# Sim7600.net
KiCad netlist of a schematic drawn in Altium Designer
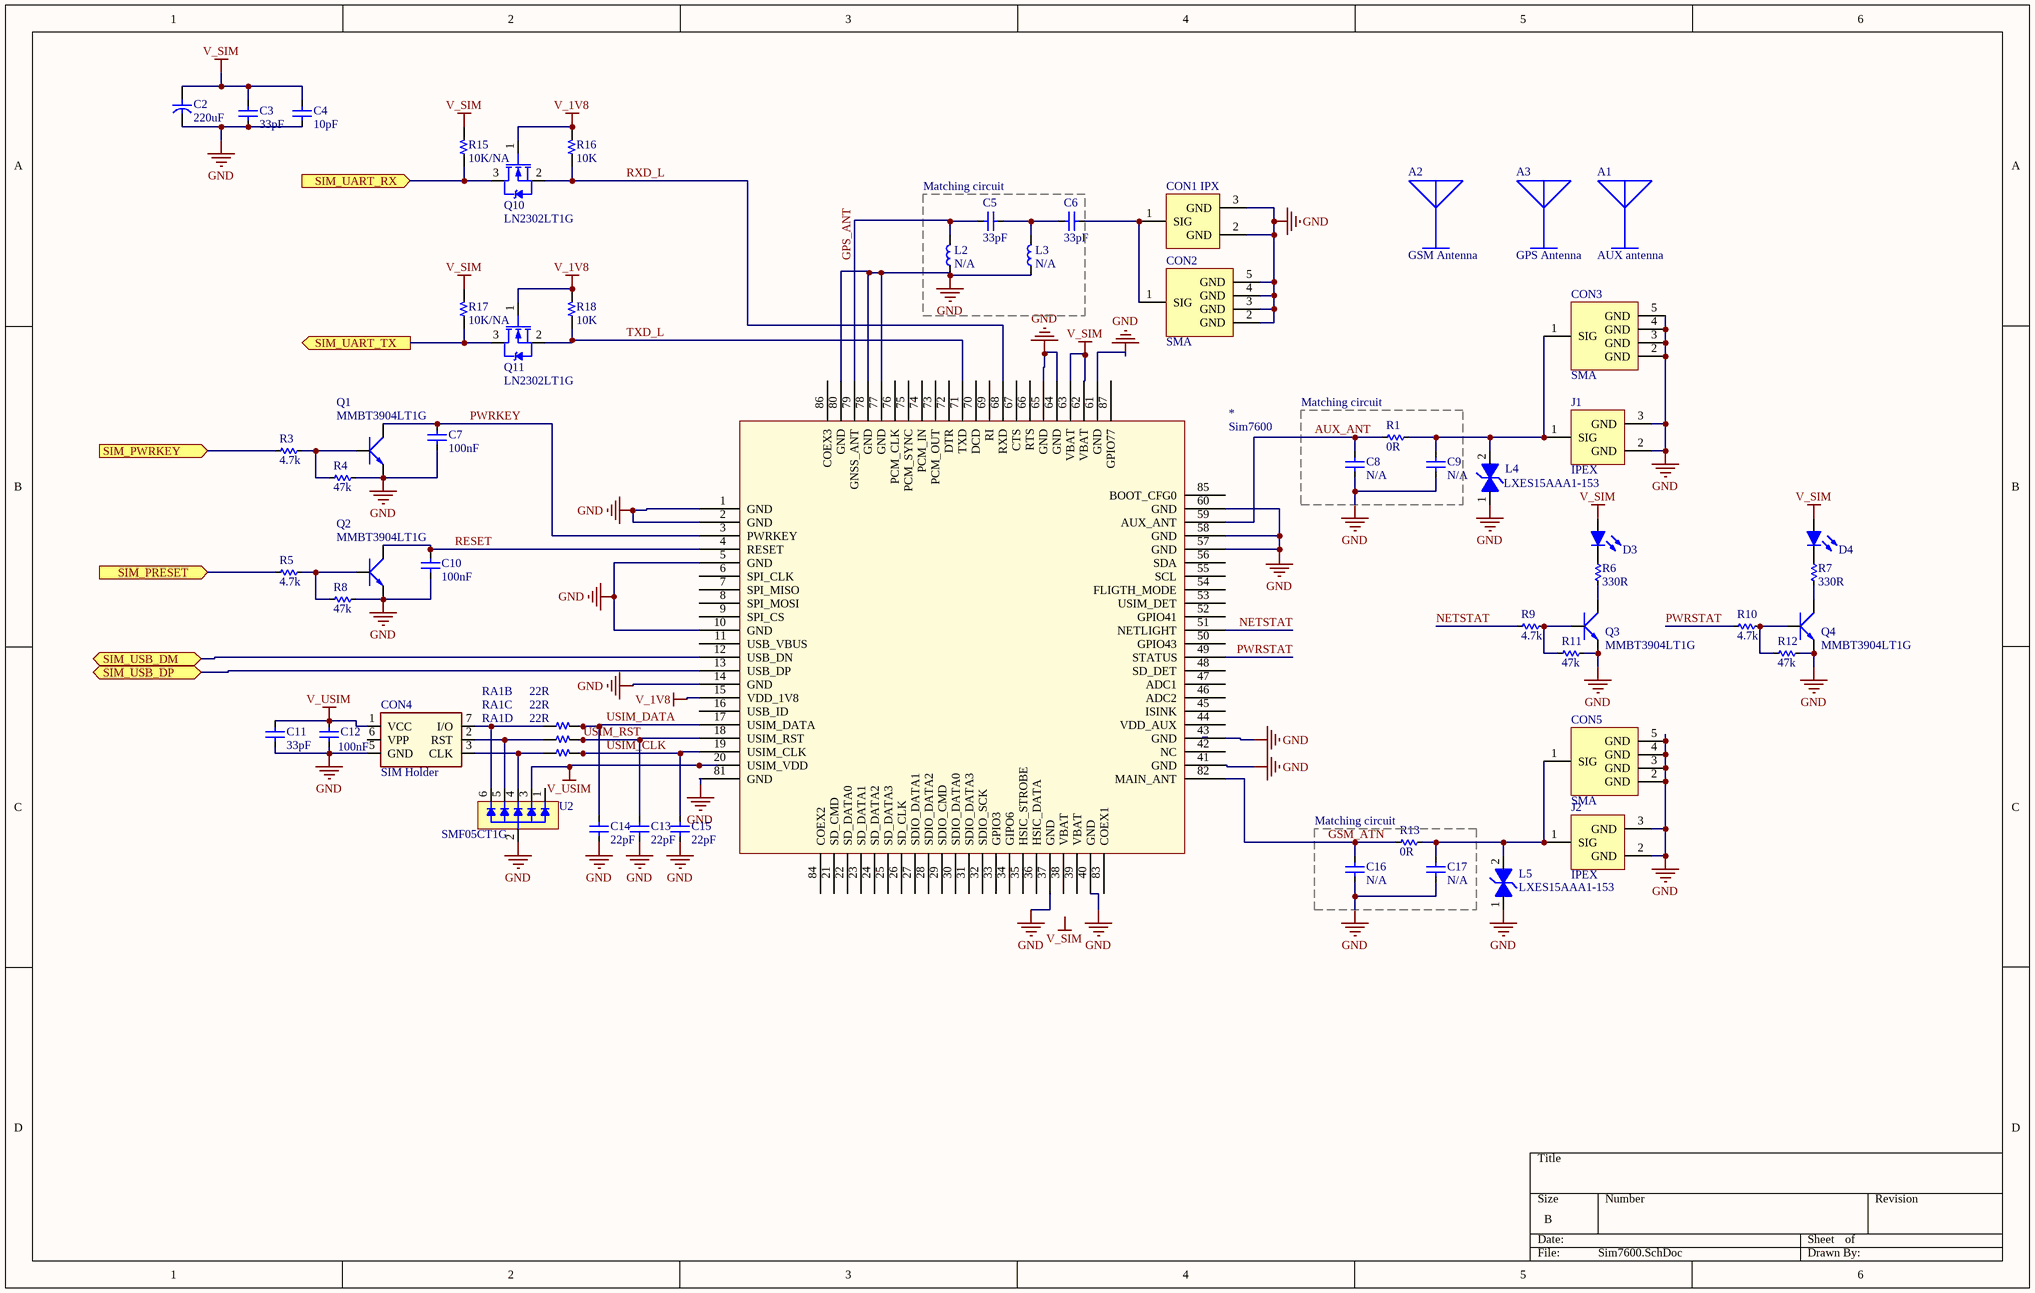
[diagram p0: Sim7600.SchDoc]

(export (version "E")
  (design (tool "Eeschema 10.0.6"))
  (components
    (comp (ref "*") (value "Sim7600") (footprint "Sim7600") (libsource (lib "Sim7600") (part "Sim7600")))
    (comp (ref "A1")
      (value "AUX antenna")
      (footprint "Antenna")
      (description "Antenna")
      (libsource (lib "car_logger_libs") (part "Antenna"))
    )
    (comp (ref "A2")
      (value "GSM Antenna")
      (footprint "Antenna")
      (description "Antenna")
      (libsource (lib "car_logger_libs") (part "Antenna"))
    )
    (comp (ref "A3")
      (value "GPS Antenna")
      (footprint "Antenna")
      (description "Antenna")
      (libsource (lib "car_logger_libs") (part "Antenna"))
    )
    (comp (ref "C2")
      (value "220uF")
      (footprint "C SMD ALU (D8)")
      (description "CAP TANT POLY 100UF 6.3V 1210")
      (fields
        (field (name "MANUFACTURER") "AVX Corporation")
        (field (name "MANUFACTURER PART NUMBER") "TCJB107M006R0055")
      )
      (libsource (lib "ChipFC_Lib") (part "Capacitor"))
    )
    (comp (ref "C3")
      (value "33pF")
      (footprint "CC 0603")
      (description "CAP CER 33PF 100V C0G/NP0 0603")
      (fields
        (field (name "MANUFACTURER") "Murata Electronics")
        (field (name "MANUFACTURER PART NUMBER") "GCM1885C2A330JA16D")
      )
      (libsource (lib "car_logger_libs") (part "Capacitor NP"))
    )
    (comp (ref "C4")
      (value "10pF")
      (footprint "CC 0603")
      (description "CAP CER 10PF 100V C0G/NP0 0603")
      (fields
        (field (name "MANUFACTURER") "Murata Electronics")
        (field (name "MANUFACTURER PART NUMBER") "GCM1885C2A100JA16D")
      )
      (libsource (lib "car_logger_libs") (part "Capacitor NP"))
    )
    (comp (ref "C5")
      (value "33pF")
      (footprint "CC 0603")
      (description "CAP CER 33PF 100V C0G/NP0 0603")
      (fields
        (field (name "MANUFACTURER") "Murata Electronics")
        (field (name "MANUFACTURER PART NUMBER") "GCM1885C2A330JA16D")
      )
      (libsource (lib "car_logger_libs") (part "Capacitor NP"))
    )
    (comp (ref "C6")
      (value "33pF")
      (footprint "CC 0603")
      (description "CAP CER 33PF 100V C0G/NP0 0603")
      (fields
        (field (name "MANUFACTURER") "Murata Electronics")
        (field (name "MANUFACTURER PART NUMBER") "GCM1885C2A330JA16D")
      )
      (libsource (lib "car_logger_libs") (part "Capacitor NP"))
    )
    (comp (ref "C7")
      (value "100nF")
      (footprint "CC 0603")
      (description "CAP CER 0.1UF 16V X7R 0603")
      (fields
        (field (name "MANUFACTURER") "Murata Electronics")
        (field (name "MANUFACTURER PART NUMBER") "GCJ188R71C104KA01D")
      )
      (libsource (lib "car_logger_libs") (part "Capacitor NP"))
    )
    (comp (ref "C8")
      (value "N/A")
      (footprint "CC 0603")
      (description "CAP N/A")
      (libsource (lib "car_logger_libs") (part "Capacitor NP"))
    )
    (comp (ref "C9")
      (value "N/A")
      (footprint "CC 0603")
      (description "CAP N/A")
      (libsource (lib "car_logger_libs") (part "Capacitor NP"))
    )
    (comp (ref "C10")
      (value "100nF")
      (footprint "CC 0603")
      (description "CAP CER 0.1UF 16V X7R 0603")
      (fields
        (field (name "MANUFACTURER") "Murata Electronics")
        (field (name "MANUFACTURER PART NUMBER") "GCJ188R71C104KA01D")
      )
      (libsource (lib "car_logger_libs") (part "Capacitor NP"))
    )
    (comp (ref "C11")
      (value "33pF")
      (footprint "CC 0603")
      (description "CAP CER 33PF 100V C0G/NP0 0603")
      (fields
        (field (name "MANUFACTURER") "Murata Electronics")
        (field (name "MANUFACTURER PART NUMBER") "GCM1885C2A330JA16D")
      )
      (libsource (lib "car_logger_libs") (part "Capacitor NP"))
    )
    (comp (ref "C12")
      (value "100nF")
      (footprint "CC 0603")
      (description "CAP CER 0.1UF 16V X7R 0603")
      (fields
        (field (name "MANUFACTURER") "Murata Electronics")
        (field (name "MANUFACTURER PART NUMBER") "GCJ188R71C104KA01D")
      )
      (libsource (lib "car_logger_libs") (part "Capacitor NP"))
    )
    (comp (ref "C13")
      (value "22pF")
      (footprint "CC 0603")
      (description "CAP CER 33PF 100V C0G/NP0 0603")
      (fields
        (field (name "MANUFACTURER") "Murata Electronics")
        (field (name "MANUFACTURER PART NUMBER") "GCM1885C2A330JA16D")
      )
      (libsource (lib "car_logger_libs") (part "Capacitor NP"))
    )
    (comp (ref "C14")
      (value "22pF")
      (footprint "CC 0603")
      (description "CAP CER 33PF 100V C0G/NP0 0603")
      (fields
        (field (name "MANUFACTURER") "Murata Electronics")
        (field (name "MANUFACTURER PART NUMBER") "GCM1885C2A330JA16D")
      )
      (libsource (lib "car_logger_libs") (part "Capacitor NP"))
    )
    (comp (ref "C15")
      (value "22pF")
      (footprint "CC 0603")
      (description "CAP CER 33PF 100V C0G/NP0 0603")
      (fields
        (field (name "MANUFACTURER") "Murata Electronics")
        (field (name "MANUFACTURER PART NUMBER") "GCM1885C2A330JA16D")
      )
      (libsource (lib "car_logger_libs") (part "Capacitor NP"))
    )
    (comp (ref "C16")
      (value "N/A")
      (footprint "CC 0603")
      (description "CAP N/A")
      (libsource (lib "car_logger_libs") (part "Capacitor NP"))
    )
    (comp (ref "C17")
      (value "N/A")
      (footprint "CC 0603")
      (description "CAP N/A")
      (libsource (lib "car_logger_libs") (part "Capacitor NP"))
    )
    (comp (ref "CON1")
      (value "IPX")
      (footprint "CONN/IPX/SMD")
      (libsource (lib "chipfc_altium_libs") (part "CON IPX"))
    )
    (comp (ref "CON2")
      (value "SMA")
      (footprint "CONN/SMA/RA")
      (description "SMA connectors")
      (libsource (lib "chipfc_altium_libs") (part "CON SMA"))
    )
    (comp (ref "CON3")
      (value "SMA")
      (footprint "CONN/SMA/RA")
      (description "SMA connectors")
      (libsource (lib "chipfc_altium_libs") (part "CON SMA"))
    )
    (comp (ref "CON4")
      (value "SIM Holder")
      (footprint "CON SIM Holder C707")
      (description "SIM Card holder, 6 pins")
      (libsource (lib "chipfc_altium_libs") (part "SIM holder 6 pin"))
    )
    (comp (ref "CON5")
      (value "SMA")
      (footprint "CONN/SMA/RA")
      (description "SMA connectors")
      (libsource (lib "chipfc_altium_libs") (part "CON SMA"))
    )
    (comp (ref "D3")
      (value "LED GREEN")
      (footprint "Led 0603 - green")
      (description "LED GREEN DIFFUSED 0603 SMD")
      (fields
        (field (name "MANUFACTURER") "Rohm Semiconductor")
        (field (name "MANUFACTURER PART NUMBER") "SML-D12P8WT86")
      )
      (libsource (lib "chipfc_altium_libs") (part "Led"))
    )
    (comp (ref "D4")
      (value "LED RED")
      (footprint "Led 0603 - red")
      (description "LED RED DIFFUSED 0603 SMD")
      (fields
        (field (name "MANUFACTURER") "Rohm Semiconductor")
        (field (name "MANUFACTURER PART NUMBER") "SML-D12U8WT86")
      )
      (libsource (lib "chipfc_altium_libs") (part "Led"))
    )
    (comp (ref "J1")
      (value "IPEX")
      (footprint "CONN/IPX/SMD")
      (description "CONN UMC RCPT STR 50 OHM SMD")
      (fields
        (field (name "MANUFACTURER") "Taoglas Limited")
        (field (name "MANUFACTURER PART NUMBER") "RECE.20279.001E.01")
      )
      (libsource (lib "chipfc_altium_libs") (part "CON IPX"))
    )
    (comp (ref "J2")
      (value "IPEX")
      (footprint "CONN/IPX/SMD")
      (description "CONN UMC RCPT STR 50 OHM SMD")
      (fields
        (field (name "MANUFACTURER") "Taoglas Limited")
        (field (name "MANUFACTURER PART NUMBER") "RECE.20279.001E.01")
      )
      (libsource (lib "chipfc_altium_libs") (part "CON IPX"))
    )
    (comp (ref "L2")
      (value "N/A")
      (footprint "LL 0603")
      (description "IND N/A")
      (libsource (lib "car_logger_libs") (part "Inductor"))
    )
    (comp (ref "L3")
      (value "N/A")
      (footprint "LL 0603")
      (description "IND N/A")
      (libsource (lib "car_logger_libs") (part "Inductor"))
    )
    (comp (ref "L4")
      (value "LXES15AAA1-153")
      (footprint "C 0603")
      (description "Clamp Ipp Tvs Diode Surface Mount 1005")
      (fields (field (name "MF") "Murata") (field (name "DIGI-KEY_PART_NUMBER") "490-13210-1-ND"))
      (libsource (lib "LXES15AAA1-153") (part "LXES15AAA1-153"))
    )
    (comp (ref "L5")
      (value "LXES15AAA1-153")
      (footprint "C 0603")
      (description "Clamp Ipp Tvs Diode Surface Mount 1005")
      (fields (field (name "MF") "Murata") (field (name "DIGI-KEY_PART_NUMBER") "490-13210-1-ND"))
      (libsource (lib "LXES15AAA1-153") (part "LXES15AAA1-153"))
    )
    (comp (ref "Q1")
      (value "MMBT3904LT1G")
      (footprint "SOT-23")
      (description "TRANS NPN 40V 0.2A SOT23")
      (fields (field (name "MANUFACTURER") "ON Semiconductor"))
      (libsource (lib "car_logger_libs") (part "MMBT3904LT1G"))
    )
    (comp (ref "Q2")
      (value "MMBT3904LT1G")
      (footprint "SOT-23")
      (description "TRANS NPN 40V 0.2A SOT23")
      (fields (field (name "MANUFACTURER") "ON Semiconductor"))
      (libsource (lib "car_logger_libs") (part "MMBT3904LT1G"))
    )
    (comp (ref "Q3")
      (value "MMBT3904LT1G")
      (footprint "SOT-23")
      (description "TRANS NPN 40V 0.2A SOT23")
      (fields (field (name "MANUFACTURER") "ON Semiconductor"))
      (libsource (lib "car_logger_libs") (part "MMBT3904LT1G"))
    )
    (comp (ref "Q4")
      (value "MMBT3904LT1G")
      (footprint "SOT-23")
      (description "TRANS NPN 40V 0.2A SOT23")
      (fields (field (name "MANUFACTURER") "ON Semiconductor"))
      (libsource (lib "car_logger_libs") (part "MMBT3904LT1G"))
    )
    (comp (ref "Q10")
      (value "LN2302LT1G")
      (footprint "SOT-23")
      (description "Mosfet N")
      (libsource (lib "chipfc_altium_libs") (part "Mosfet N"))
    )
    (comp (ref "Q11")
      (value "LN2302LT1G")
      (footprint "SOT-23")
      (description "Mosfet N")
      (libsource (lib "chipfc_altium_libs") (part "Mosfet N"))
    )
    (comp (ref "R1")
      (value "0R")
      (footprint "RR 0603")
      (description "RES SMD 0 OHM JUMPER 1/10W 0603")
      (fields
        (field (name "MANUFACTURER") "Panasonic Industrial Devices")
        (field (name "MANUFACTURER PART NUMBER") "ERJ-3GEY0R00V")
      )
      (libsource (lib "car_logger_libs") (part "Resistors"))
    )
    (comp (ref "R3")
      (value "4.7k")
      (footprint "RR 0603")
      (description "RES SMD 4.7K OHM 1% 1/10W 0603")
      (fields
        (field (name "MANUFACTURER") "Panasonic Industrial Devices")
        (field (name "MANUFACTURER PART NUMBER") "ERJ-3EKF4701V")
      )
      (libsource (lib "car_logger_libs") (part "Resistors"))
    )
    (comp (ref "R4")
      (value "47k")
      (footprint "RR 0603")
      (description "RES SMD 47K OHM 5% 1/10W 0603")
      (fields
        (field (name "MANUFACTURER") "Panasonic Industrial Devices")
        (field (name "MANUFACTURER PART NUMBER") "ERJ-3GEYJ473V")
      )
      (libsource (lib "car_logger_libs") (part "Resistors"))
    )
    (comp (ref "R5")
      (value "4.7k")
      (footprint "RR 0603")
      (description "RES SMD 4.7K OHM 1% 1/10W 0603")
      (fields
        (field (name "MANUFACTURER") "Panasonic Industrial Devices")
        (field (name "MANUFACTURER PART NUMBER") "ERJ-3EKF4701V")
      )
      (libsource (lib "car_logger_libs") (part "Resistors"))
    )
    (comp (ref "R6")
      (value "330R")
      (footprint "RR 0603")
      (description "RES SMD 330 OHM 5% 1/10W 0603")
      (fields
        (field (name "MANUFACTURER") "Panasonic Industrial Devices")
        (field (name "MANUFACTURER PART NUMBER") "ERJ-3GEYJ331V")
      )
      (libsource (lib "car_logger_libs") (part "Resistors"))
    )
    (comp (ref "R7")
      (value "330R")
      (footprint "RR 0603")
      (description "RES SMD 330 OHM 5% 1/10W 0603")
      (fields
        (field (name "MANUFACTURER") "Panasonic Industrial Devices")
        (field (name "MANUFACTURER PART NUMBER") "ERJ-3GEYJ331V")
      )
      (libsource (lib "car_logger_libs") (part "Resistors"))
    )
    (comp (ref "R8")
      (value "47k")
      (footprint "RR 0603")
      (description "RES SMD 47K OHM 5% 1/10W 0603")
      (fields
        (field (name "MANUFACTURER") "Panasonic Industrial Devices")
        (field (name "MANUFACTURER PART NUMBER") "ERJ-3GEYJ473V")
      )
      (libsource (lib "car_logger_libs") (part "Resistors"))
    )
    (comp (ref "R9")
      (value "4.7k")
      (footprint "RR 0603")
      (description "RES SMD 4.7K OHM 1% 1/10W 0603")
      (fields
        (field (name "MANUFACTURER") "Panasonic Industrial Devices")
        (field (name "MANUFACTURER PART NUMBER") "ERJ-3EKF4701V")
      )
      (libsource (lib "car_logger_libs") (part "Resistors"))
    )
    (comp (ref "R10")
      (value "4.7k")
      (footprint "RR 0603")
      (description "RES SMD 4.7K OHM 1% 1/10W 0603")
      (fields
        (field (name "MANUFACTURER") "Panasonic Industrial Devices")
        (field (name "MANUFACTURER PART NUMBER") "ERJ-3EKF4701V")
      )
      (libsource (lib "car_logger_libs") (part "Resistors"))
    )
    (comp (ref "R11")
      (value "47k")
      (footprint "RR 0603")
      (description "RES SMD 47K OHM 5% 1/10W 0603")
      (fields
        (field (name "MANUFACTURER") "Panasonic Industrial Devices")
        (field (name "MANUFACTURER PART NUMBER") "ERJ-3GEYJ473V")
      )
      (libsource (lib "car_logger_libs") (part "Resistors"))
    )
    (comp (ref "R12")
      (value "47k")
      (footprint "RR 0603")
      (description "RES SMD 47K OHM 5% 1/10W 0603")
      (fields
        (field (name "MANUFACTURER") "Panasonic Industrial Devices")
        (field (name "MANUFACTURER PART NUMBER") "ERJ-3GEYJ473V")
      )
      (libsource (lib "car_logger_libs") (part "Resistors"))
    )
    (comp (ref "R13")
      (value "0R")
      (footprint "RR 0603")
      (description "RES SMD 0 OHM JUMPER 1/10W 0603")
      (fields
        (field (name "MANUFACTURER") "Panasonic Industrial Devices")
        (field (name "MANUFACTURER PART NUMBER") "ERJ-3GEY0R00V")
      )
      (libsource (lib "car_logger_libs") (part "Resistors"))
    )
    (comp (ref "R15")
      (value "10K/NA")
      (footprint "R 0603")
      (description "Resistor")
      (libsource (lib "chipfc_altium_libs") (part "Resistor"))
    )
    (comp (ref "R16")
      (value "10K")
      (footprint "R 0603")
      (description "Resistor")
      (libsource (lib "chipfc_altium_libs") (part "Resistor"))
    )
    (comp (ref "R17")
      (value "10K/NA")
      (footprint "R 0603")
      (description "Resistor")
      (libsource (lib "chipfc_altium_libs") (part "Resistor"))
    )
    (comp (ref "R18")
      (value "10K")
      (footprint "R 0603")
      (description "Resistor")
      (libsource (lib "chipfc_altium_libs") (part "Resistor"))
    )
    (comp (ref "RA1")
      (value "22R")
      (footprint "RAx4 1206 (3216)")
      (libsource (lib "chipfc_altium_libs") (part "Resistor Array x4"))
    )
    (comp (ref "U2")
      (value "SMF05CT1G")
      (footprint "SOT-363-6")
      (description "TVS DIODE 5V 12.5V SC88")
      (fields (field (name "MANUFACTURER") "ON Semiconductor"))
      (libsource (lib "car_logger_libs") (part "SMF05C"))
    )
  )
  (nets
    (net (code "1") (name "/AUX_ANT") (class "Default")
      (node (ref "*") (pin "59") (pinfunction "AUX_ANT_59") (pintype "passive"))
      (node (ref "C8") (pin "2") (pinfunction "2_2") (pintype "passive"))
      (node (ref "R1") (pin "2") (pinfunction "2_2") (pintype "passive"))
    )
    (net (code "2") (name "/GPS_ANT") (class "Default")
      (node (ref "*") (pin "79") (pinfunction "GNSS_ANT_79") (pintype "passive"))
      (node (ref "C5") (pin "2") (pinfunction "2_2") (pintype "passive"))
      (node (ref "L2") (pin "2") (pinfunction "2_2") (pintype "passive"))
    )
    (net (code "3") (name "/GSM_ATN") (class "Default")
      (node (ref "*") (pin "82") (pinfunction "MAIN_ANT_82") (pintype "passive"))
      (node (ref "C16") (pin "2") (pinfunction "2_2") (pintype "passive"))
      (node (ref "R13") (pin "2") (pinfunction "2_2") (pintype "passive"))
    )
    (net (code "4") (name "/NETSTAT") (class "Default")
      (node (ref "*") (pin "51") (pinfunction "NETLIGHT_51") (pintype "passive"))
      (node (ref "R9") (pin "1") (pinfunction "1_1") (pintype "passive"))
    )
    (net (code "5") (name "/PWRKEY") (class "Default")
      (node (ref "*") (pin "3") (pinfunction "PWRKEY_3") (pintype "passive"))
      (node (ref "C7") (pin "1") (pinfunction "1_1") (pintype "passive"))
      (node (ref "Q1") (pin "3") (pinfunction "C_3") (pintype "passive"))
    )
    (net (code "6") (name "/PWRSTAT") (class "Default")
      (node (ref "*") (pin "49") (pinfunction "STATUS_49") (pintype "passive"))
      (node (ref "R10") (pin "1") (pinfunction "1_1") (pintype "passive"))
    )
    (net (code "7") (name "/RESET") (class "Default")
      (node (ref "*") (pin "4") (pinfunction "RESET_4") (pintype "passive"))
      (node (ref "C10") (pin "1") (pinfunction "1_1") (pintype "passive"))
      (node (ref "Q2") (pin "3") (pinfunction "C_3") (pintype "passive"))
    )
    (net (code "8") (name "/RXD_L") (class "Default")
      (node (ref "*") (pin "68") (pinfunction "RXD_68") (pintype "passive"))
      (node (ref "Q10") (pin "2") (pinfunction "S_2") (pintype "passive"))
      (node (ref "R16") (pin "1") (pinfunction "1_1") (pintype "passive"))
    )
    (net (code "9") (name "/SIM_PRESET") (class "Default")
      (node (ref "R5") (pin "1") (pinfunction "1_1") (pintype "passive"))
    )
    (net (code "10") (name "/SIM_PWRKEY") (class "Default")
      (node (ref "R3") (pin "1") (pinfunction "1_1") (pintype "passive"))
    )
    (net (code "11") (name "/SIM_UART_RX") (class "Default")
      (node (ref "Q10") (pin "3") (pinfunction "D_3") (pintype "passive"))
      (node (ref "R15") (pin "1") (pinfunction "1_1") (pintype "passive"))
    )
    (net (code "12") (name "/SIM_UART_TX") (class "Default")
      (node (ref "Q11") (pin "3") (pinfunction "D_3") (pintype "passive"))
      (node (ref "R17") (pin "1") (pinfunction "1_1") (pintype "passive"))
    )
    (net (code "13") (name "/SIM_USB_DM") (class "Default")
      (node (ref "*") (pin "12") (pinfunction "USB_DN_12") (pintype "passive"))
    )
    (net (code "14") (name "/SIM_USB_DP") (class "Default")
      (node (ref "*") (pin "13") (pinfunction "USB_DP_13") (pintype "passive"))
    )
    (net (code "15") (name "/TXD_L") (class "Default")
      (node (ref "*") (pin "71") (pinfunction "TXD_71") (pintype "passive"))
      (node (ref "Q11") (pin "2") (pinfunction "S_2") (pintype "passive"))
      (node (ref "R18") (pin "1") (pinfunction "1_1") (pintype "passive"))
    )
    (net (code "16") (name "/USIM_CLK") (class "Default")
      (node (ref "*") (pin "19") (pinfunction "USIM_CLK_19") (pintype "passive"))
      (node (ref "C15") (pin "1") (pinfunction "1_1") (pintype "passive"))
      (node (ref "RA1") (pin "5") (pinfunction "5_5") (pintype "passive"))
    )
    (net (code "17") (name "/USIM_DATA") (class "Default")
      (node (ref "*") (pin "17") (pinfunction "USIM_DATA_17") (pintype "passive"))
      (node (ref "C14") (pin "1") (pinfunction "1_1") (pintype "passive"))
      (node (ref "RA1") (pin "7") (pinfunction "7_7") (pintype "passive"))
    )
    (net (code "18") (name "/USIM_RST") (class "Default")
      (node (ref "*") (pin "18") (pinfunction "USIM_RST_18") (pintype "passive"))
      (node (ref "C13") (pin "1") (pinfunction "1_1") (pintype "passive"))
      (node (ref "RA1") (pin "6") (pinfunction "6_6") (pintype "passive"))
    )
    (net (code "19") (name "GND") (class "Default")
      (node (ref "*") (pin "1") (pinfunction "GND_1") (pintype "passive"))
      (node (ref "*") (pin "10") (pinfunction "GND_10") (pintype "passive"))
      (node (ref "*") (pin "14") (pinfunction "GND_14") (pintype "passive"))
      (node (ref "*") (pin "2") (pinfunction "GND_2") (pintype "passive"))
      (node (ref "*") (pin "37") (pinfunction "GND_37") (pintype "passive"))
      (node (ref "*") (pin "40") (pinfunction "GND_40") (pintype "passive"))
      (node (ref "*") (pin "41") (pinfunction "GND_41") (pintype "passive"))
      (node (ref "*") (pin "43") (pinfunction "GND_43") (pintype "passive"))
      (node (ref "*") (pin "5") (pinfunction "GND_5") (pintype "passive"))
      (node (ref "*") (pin "57") (pinfunction "GND_57") (pintype "passive"))
      (node (ref "*") (pin "58") (pinfunction "GND_58") (pintype "passive"))
      (node (ref "*") (pin "60") (pinfunction "GND_60") (pintype "passive"))
      (node (ref "*") (pin "61") (pinfunction "GND_61") (pintype "passive"))
      (node (ref "*") (pin "64") (pinfunction "GND_64") (pintype "passive"))
      (node (ref "*") (pin "65") (pinfunction "GND_65") (pintype "passive"))
      (node (ref "*") (pin "77") (pinfunction "GND_77") (pintype "passive"))
      (node (ref "*") (pin "78") (pinfunction "GND_78") (pintype "passive"))
      (node (ref "*") (pin "80") (pinfunction "GND_80") (pintype "passive"))
      (node (ref "*") (pin "81") (pinfunction "GND_81") (pintype "passive"))
      (node (ref "C10") (pin "2") (pinfunction "2_2") (pintype "passive"))
      (node (ref "C11") (pin "2") (pinfunction "2_2") (pintype "passive"))
      (node (ref "C12") (pin "2") (pinfunction "2_2") (pintype "passive"))
      (node (ref "C13") (pin "2") (pinfunction "2_2") (pintype "passive"))
      (node (ref "C14") (pin "2") (pinfunction "2_2") (pintype "passive"))
      (node (ref "C15") (pin "2") (pinfunction "2_2") (pintype "passive"))
      (node (ref "C16") (pin "1") (pinfunction "1_1") (pintype "passive"))
      (node (ref "C17") (pin "1") (pinfunction "1_1") (pintype "passive"))
      (node (ref "C2") (pin "2") (pinfunction "2_2") (pintype "passive"))
      (node (ref "C3") (pin "1") (pinfunction "1_1") (pintype "passive"))
      (node (ref "C4") (pin "1") (pinfunction "1_1") (pintype "passive"))
      (node (ref "C7") (pin "2") (pinfunction "2_2") (pintype "passive"))
      (node (ref "C8") (pin "1") (pinfunction "1_1") (pintype "passive"))
      (node (ref "C9") (pin "1") (pinfunction "1_1") (pintype "passive"))
      (node (ref "CON1") (pin "2") (pinfunction "GND_2") (pintype "passive"))
      (node (ref "CON1") (pin "3") (pinfunction "GND_3") (pintype "passive"))
      (node (ref "CON2") (pin "2") (pinfunction "GND_2") (pintype "passive"))
      (node (ref "CON2") (pin "3") (pinfunction "GND_3") (pintype "passive"))
      (node (ref "CON2") (pin "4") (pinfunction "GND_4") (pintype "passive"))
      (node (ref "CON2") (pin "5") (pinfunction "GND_5") (pintype "passive"))
      (node (ref "CON3") (pin "2") (pinfunction "GND_2") (pintype "passive"))
      (node (ref "CON3") (pin "3") (pinfunction "GND_3") (pintype "passive"))
      (node (ref "CON3") (pin "4") (pinfunction "GND_4") (pintype "passive"))
      (node (ref "CON3") (pin "5") (pinfunction "GND_5") (pintype "passive"))
      (node (ref "CON4") (pin "5") (pinfunction "GND_5") (pintype "power_in"))
      (node (ref "CON5") (pin "2") (pinfunction "GND_2") (pintype "passive"))
      (node (ref "CON5") (pin "3") (pinfunction "GND_3") (pintype "passive"))
      (node (ref "CON5") (pin "4") (pinfunction "GND_4") (pintype "passive"))
      (node (ref "CON5") (pin "5") (pinfunction "GND_5") (pintype "passive"))
      (node (ref "J1") (pin "2") (pinfunction "GND_2") (pintype "passive"))
      (node (ref "J1") (pin "3") (pinfunction "GND_3") (pintype "passive"))
      (node (ref "J2") (pin "2") (pinfunction "GND_2") (pintype "passive"))
      (node (ref "J2") (pin "3") (pinfunction "GND_3") (pintype "passive"))
      (node (ref "L2") (pin "1") (pinfunction "1_1") (pintype "passive"))
      (node (ref "L3") (pin "1") (pinfunction "1_1") (pintype "passive"))
      (node (ref "L4") (pin "1") (pinfunction "1_1") (pintype "passive"))
      (node (ref "L5") (pin "1") (pinfunction "1_1") (pintype "passive"))
      (node (ref "Q1") (pin "2") (pinfunction "E_2") (pintype "passive"))
      (node (ref "Q2") (pin "2") (pinfunction "E_2") (pintype "passive"))
      (node (ref "Q3") (pin "2") (pinfunction "E_2") (pintype "passive"))
      (node (ref "Q4") (pin "2") (pinfunction "E_2") (pintype "passive"))
      (node (ref "R11") (pin "2") (pinfunction "2_2") (pintype "passive"))
      (node (ref "R12") (pin "2") (pinfunction "2_2") (pintype "passive"))
      (node (ref "R4") (pin "2") (pinfunction "2_2") (pintype "passive"))
      (node (ref "R8") (pin "2") (pinfunction "2_2") (pintype "passive"))
      (node (ref "U2") (pin "2") (pinfunction "A_2") (pintype "passive"))
    )
    (net (code "20") (name "Net-(C5-Pad1)") (class "Default")
      (node (ref "C5") (pin "1") (pinfunction "1_1") (pintype "passive"))
      (node (ref "C6") (pin "2") (pinfunction "2_2") (pintype "passive"))
      (node (ref "L3") (pin "2") (pinfunction "2_2") (pintype "passive"))
    )
    (net (code "21") (name "Net-(CON1-SIG)") (class "Default")
      (node (ref "C6") (pin "1") (pinfunction "1_1") (pintype "passive"))
      (node (ref "CON1") (pin "1") (pinfunction "SIG_1") (pintype "passive"))
      (node (ref "CON2") (pin "1") (pinfunction "SIG_1") (pintype "passive"))
    )
    (net (code "22") (name "Net-(CON3-SIG)") (class "Default")
      (node (ref "C9") (pin "2") (pinfunction "2_2") (pintype "passive"))
      (node (ref "CON3") (pin "1") (pinfunction "SIG_1") (pintype "passive"))
      (node (ref "J1") (pin "1") (pinfunction "SIG_1") (pintype "passive"))
      (node (ref "L4") (pin "2") (pinfunction "2_2") (pintype "passive"))
      (node (ref "R1") (pin "1") (pinfunction "1_1") (pintype "passive"))
    )
    (net (code "23") (name "Net-(CON4-CLK)") (class "Default")
      (node (ref "CON4") (pin "3") (pinfunction "CLK_3") (pintype "passive"))
      (node (ref "RA1") (pin "4") (pinfunction "4_4") (pintype "passive"))
      (node (ref "U2") (pin "4") (pinfunction "K4_4") (pintype "passive"))
    )
    (net (code "24") (name "Net-(CON4-I{slash}O)") (class "Default")
      (node (ref "CON4") (pin "7") (pinfunction "I/O_7") (pintype "passive"))
      (node (ref "RA1") (pin "2") (pinfunction "2_2") (pintype "passive"))
      (node (ref "U2") (pin "6") (pinfunction "K6_6") (pintype "passive"))
    )
    (net (code "25") (name "Net-(CON4-RST)") (class "Default")
      (node (ref "CON4") (pin "2") (pinfunction "RST_2") (pintype "passive"))
      (node (ref "RA1") (pin "3") (pinfunction "3_3") (pintype "passive"))
      (node (ref "U2") (pin "5") (pinfunction "K5_5") (pintype "passive"))
    )
    (net (code "26") (name "Net-(CON5-SIG)") (class "Default")
      (node (ref "C17") (pin "2") (pinfunction "2_2") (pintype "passive"))
      (node (ref "CON5") (pin "1") (pinfunction "SIG_1") (pintype "passive"))
      (node (ref "J2") (pin "1") (pinfunction "SIG_1") (pintype "passive"))
      (node (ref "L5") (pin "2") (pinfunction "2_2") (pintype "passive"))
      (node (ref "R13") (pin "1") (pinfunction "1_1") (pintype "passive"))
    )
    (net (code "27") (name "Net-(D3-K)") (class "Default")
      (node (ref "D3") (pin "2") (pinfunction "K_2") (pintype "passive"))
      (node (ref "R6") (pin "2") (pinfunction "2_2") (pintype "passive"))
    )
    (net (code "28") (name "Net-(D4-K)") (class "Default")
      (node (ref "D4") (pin "2") (pinfunction "K_2") (pintype "passive"))
      (node (ref "R7") (pin "2") (pinfunction "2_2") (pintype "passive"))
    )
    (net (code "29") (name "Net-(Q1-B)") (class "Default")
      (node (ref "Q1") (pin "1") (pinfunction "B_1") (pintype "passive"))
      (node (ref "R3") (pin "2") (pinfunction "2_2") (pintype "passive"))
      (node (ref "R4") (pin "1") (pinfunction "1_1") (pintype "passive"))
    )
    (net (code "30") (name "Net-(Q2-B)") (class "Default")
      (node (ref "Q2") (pin "1") (pinfunction "B_1") (pintype "passive"))
      (node (ref "R5") (pin "2") (pinfunction "2_2") (pintype "passive"))
      (node (ref "R8") (pin "1") (pinfunction "1_1") (pintype "passive"))
    )
    (net (code "31") (name "Net-(Q3-B)") (class "Default")
      (node (ref "Q3") (pin "1") (pinfunction "B_1") (pintype "passive"))
      (node (ref "R11") (pin "1") (pinfunction "1_1") (pintype "passive"))
      (node (ref "R9") (pin "2") (pinfunction "2_2") (pintype "passive"))
    )
    (net (code "32") (name "Net-(Q3-C)") (class "Default")
      (node (ref "Q3") (pin "3") (pinfunction "C_3") (pintype "passive"))
      (node (ref "R6") (pin "1") (pinfunction "1_1") (pintype "passive"))
    )
    (net (code "33") (name "Net-(Q4-B)") (class "Default")
      (node (ref "Q4") (pin "1") (pinfunction "B_1") (pintype "passive"))
      (node (ref "R10") (pin "2") (pinfunction "2_2") (pintype "passive"))
      (node (ref "R12") (pin "1") (pinfunction "1_1") (pintype "passive"))
    )
    (net (code "34") (name "Net-(Q4-C)") (class "Default")
      (node (ref "Q4") (pin "3") (pinfunction "C_3") (pintype "passive"))
      (node (ref "R7") (pin "1") (pinfunction "1_1") (pintype "passive"))
    )
    (net (code "35") (name "V_1V8") (class "Default")
      (node (ref "*") (pin "15") (pinfunction "VDD_1V8_15") (pintype "passive"))
      (node (ref "Q10") (pin "1") (pinfunction "G_1") (pintype "passive"))
      (node (ref "Q11") (pin "1") (pinfunction "G_1") (pintype "passive"))
      (node (ref "R16") (pin "2") (pinfunction "2_2") (pintype "passive"))
      (node (ref "R18") (pin "2") (pinfunction "2_2") (pintype "passive"))
    )
    (net (code "36") (name "V_SIM") (class "Default")
      (node (ref "*") (pin "62") (pinfunction "VBAT_62") (pintype "passive"))
      (node (ref "*") (pin "63") (pinfunction "VBAT_63") (pintype "passive"))
      (node (ref "C2") (pin "1") (pinfunction "1_1") (pintype "passive"))
      (node (ref "C3") (pin "2") (pinfunction "2_2") (pintype "passive"))
      (node (ref "C4") (pin "2") (pinfunction "2_2") (pintype "passive"))
      (node (ref "D3") (pin "1") (pinfunction "A_1") (pintype "passive"))
      (node (ref "D4") (pin "1") (pinfunction "A_1") (pintype "passive"))
      (node (ref "R15") (pin "2") (pinfunction "2_2") (pintype "passive"))
      (node (ref "R17") (pin "2") (pinfunction "2_2") (pintype "passive"))
    )
    (net (code "37") (name "V_USIM") (class "Default")
      (node (ref "*") (pin "20") (pinfunction "USIM_VDD_20") (pintype "passive"))
      (node (ref "C11") (pin "1") (pinfunction "1_1") (pintype "passive"))
      (node (ref "C12") (pin "1") (pinfunction "1_1") (pintype "passive"))
      (node (ref "CON4") (pin "1") (pinfunction "VCC_1") (pintype "power_in"))
      (node (ref "U2") (pin "3") (pinfunction "K3_3") (pintype "passive"))
    )
    (net (code "38") (name "unconnected-(*-ADC1-Pad47)") (class "Default")
      (node (ref "*") (pin "47") (pinfunction "ADC1_47") (pintype "passive"))
    )
    (net (code "39") (name "unconnected-(*-ADC2-Pad46)") (class "Default")
      (node (ref "*") (pin "46") (pinfunction "ADC2_46") (pintype "passive"))
    )
    (net (code "40") (name "unconnected-(*-BOOT_CFG0-Pad85)") (class "Default")
      (node (ref "*") (pin "85") (pinfunction "BOOT_CFG0_85") (pintype "passive"))
    )
    (net (code "41") (name "unconnected-(*-COEX1-Pad83)") (class "Default")
      (node (ref "*") (pin "83") (pinfunction "COEX1_83") (pintype "passive"))
    )
    (net (code "42") (name "unconnected-(*-COEX2-Pad84)") (class "Default")
      (node (ref "*") (pin "84") (pinfunction "COEX2_84") (pintype "passive"))
    )
    (net (code "43") (name "unconnected-(*-COEX3-Pad86)") (class "Default")
      (node (ref "*") (pin "86") (pinfunction "COEX3_86") (pintype "passive"))
    )
    (net (code "44") (name "unconnected-(*-CTS-Pad67)") (class "Default")
      (node (ref "*") (pin "67") (pinfunction "CTS_67") (pintype "passive"))
    )
    (net (code "45") (name "unconnected-(*-DCD-Pad70)") (class "Default")
      (node (ref "*") (pin "70") (pinfunction "DCD_70") (pintype "passive"))
    )
    (net (code "46") (name "unconnected-(*-DTR-Pad72)") (class "Default")
      (node (ref "*") (pin "72") (pinfunction "DTR_72") (pintype "passive"))
    )
    (net (code "47") (name "unconnected-(*-FLIGTH_MODE-Pad54)") (class "Default")
      (node (ref "*") (pin "54") (pinfunction "FLIGTH_MODE_54") (pintype "passive"))
    )
    (net (code "48") (name "unconnected-(*-GIPO6-Pad34)") (class "Default")
      (node (ref "*") (pin "34") (pinfunction "GIPO6_34") (pintype "passive"))
    )
    (net (code "49") (name "unconnected-(*-GPIO3-Pad33)") (class "Default")
      (node (ref "*") (pin "33") (pinfunction "GPIO3_33") (pintype "passive"))
    )
    (net (code "50") (name "unconnected-(*-GPIO41-Pad52)") (class "Default")
      (node (ref "*") (pin "52") (pinfunction "GPIO41_52") (pintype "passive"))
    )
    (net (code "51") (name "unconnected-(*-GPIO43-Pad50)") (class "Default")
      (node (ref "*") (pin "50") (pinfunction "GPIO43_50") (pintype "passive"))
    )
    (net (code "52") (name "unconnected-(*-GPIO77-Pad87)") (class "Default")
      (node (ref "*") (pin "87") (pinfunction "GPIO77_87") (pintype "passive"))
    )
    (net (code "53") (name "unconnected-(*-HSIC_DATA-Pad36)") (class "Default")
      (node (ref "*") (pin "36") (pinfunction "HSIC_DATA_36") (pintype "passive"))
    )
    (net (code "54") (name "unconnected-(*-HSIC_STROBE-Pad35)") (class "Default")
      (node (ref "*") (pin "35") (pinfunction "HSIC_STROBE_35") (pintype "passive"))
    )
    (net (code "55") (name "unconnected-(*-ISINK-Pad45)") (class "Default")
      (node (ref "*") (pin "45") (pinfunction "ISINK_45") (pintype "passive"))
    )
    (net (code "56") (name "unconnected-(*-NC-Pad42)") (class "Default")
      (node (ref "*") (pin "42") (pinfunction "NC_42") (pintype "passive"))
    )
    (net (code "57") (name "unconnected-(*-PCM_CLK-Pad76)") (class "Default")
      (node (ref "*") (pin "76") (pinfunction "PCM_CLK_76") (pintype "passive"))
    )
    (net (code "58") (name "unconnected-(*-PCM_IN-Pad74)") (class "Default")
      (node (ref "*") (pin "74") (pinfunction "PCM_IN_74") (pintype "passive"))
    )
    (net (code "59") (name "unconnected-(*-PCM_OUT-Pad73)") (class "Default")
      (node (ref "*") (pin "73") (pinfunction "PCM_OUT_73") (pintype "passive"))
    )
    (net (code "60") (name "unconnected-(*-PCM_SYNC-Pad75)") (class "Default")
      (node (ref "*") (pin "75") (pinfunction "PCM_SYNC_75") (pintype "passive"))
    )
    (net (code "61") (name "unconnected-(*-RI-Pad69)") (class "Default")
      (node (ref "*") (pin "69") (pinfunction "RI_69") (pintype "passive"))
    )
    (net (code "62") (name "unconnected-(*-RTS-Pad66)") (class "Default")
      (node (ref "*") (pin "66") (pinfunction "RTS_66") (pintype "passive"))
    )
    (net (code "63") (name "unconnected-(*-SCL-Pad55)") (class "Default")
      (node (ref "*") (pin "55") (pinfunction "SCL_55") (pintype "passive"))
    )
    (net (code "64") (name "unconnected-(*-SDA-Pad56)") (class "Default")
      (node (ref "*") (pin "56") (pinfunction "SDA_56") (pintype "passive"))
    )
    (net (code "65") (name "unconnected-(*-SDIO_CMD-Pad29)") (class "Default")
      (node (ref "*") (pin "29") (pinfunction "SDIO_CMD_29") (pintype "passive"))
    )
    (net (code "66") (name "unconnected-(*-SDIO_DATA0-Pad30)") (class "Default")
      (node (ref "*") (pin "30") (pinfunction "SDIO_DATA0_30") (pintype "passive"))
    )
    (net (code "67") (name "unconnected-(*-SDIO_DATA1-Pad27)") (class "Default")
      (node (ref "*") (pin "27") (pinfunction "SDIO_DATA1_27") (pintype "passive"))
    )
    (net (code "68") (name "unconnected-(*-SDIO_DATA2-Pad28)") (class "Default")
      (node (ref "*") (pin "28") (pinfunction "SDIO_DATA2_28") (pintype "passive"))
    )
    (net (code "69") (name "unconnected-(*-SDIO_DATA3-Pad31)") (class "Default")
      (node (ref "*") (pin "31") (pinfunction "SDIO_DATA3_31") (pintype "passive"))
    )
    (net (code "70") (name "unconnected-(*-SDIO_SCK-Pad32)") (class "Default")
      (node (ref "*") (pin "32") (pinfunction "SDIO_SCK_32") (pintype "passive"))
    )
    (net (code "71") (name "unconnected-(*-SD_CLK-Pad26)") (class "Default")
      (node (ref "*") (pin "26") (pinfunction "SD_CLK_26") (pintype "passive"))
    )
    (net (code "72") (name "unconnected-(*-SD_CMD-Pad21)") (class "Default")
      (node (ref "*") (pin "21") (pinfunction "SD_CMD_21") (pintype "passive"))
    )
    (net (code "73") (name "unconnected-(*-SD_DATA0-Pad22)") (class "Default")
      (node (ref "*") (pin "22") (pinfunction "SD_DATA0_22") (pintype "passive"))
    )
    (net (code "74") (name "unconnected-(*-SD_DATA1-Pad23)") (class "Default")
      (node (ref "*") (pin "23") (pinfunction "SD_DATA1_23") (pintype "passive"))
    )
    (net (code "75") (name "unconnected-(*-SD_DATA2-Pad24)") (class "Default")
      (node (ref "*") (pin "24") (pinfunction "SD_DATA2_24") (pintype "passive"))
    )
    (net (code "76") (name "unconnected-(*-SD_DATA3-Pad25)") (class "Default")
      (node (ref "*") (pin "25") (pinfunction "SD_DATA3_25") (pintype "passive"))
    )
    (net (code "77") (name "unconnected-(*-SD_DET-Pad48)") (class "Default")
      (node (ref "*") (pin "48") (pinfunction "SD_DET_48") (pintype "passive"))
    )
    (net (code "78") (name "unconnected-(*-SPI_CLK-Pad6)") (class "Default")
      (node (ref "*") (pin "6") (pinfunction "SPI_CLK_6") (pintype "passive"))
    )
    (net (code "79") (name "unconnected-(*-SPI_CS-Pad9)") (class "Default")
      (node (ref "*") (pin "9") (pinfunction "SPI_CS_9") (pintype "passive"))
    )
    (net (code "80") (name "unconnected-(*-SPI_MISO-Pad7)") (class "Default")
      (node (ref "*") (pin "7") (pinfunction "SPI_MISO_7") (pintype "passive"))
    )
    (net (code "81") (name "unconnected-(*-SPI_MOSI-Pad8)") (class "Default")
      (node (ref "*") (pin "8") (pinfunction "SPI_MOSI_8") (pintype "passive"))
    )
    (net (code "82") (name "unconnected-(*-USB_ID-Pad16)") (class "Default")
      (node (ref "*") (pin "16") (pinfunction "USB_ID_16") (pintype "passive"))
    )
    (net (code "83") (name "unconnected-(*-USB_VBUS-Pad11)") (class "Default")
      (node (ref "*") (pin "11") (pinfunction "USB_VBUS_11") (pintype "passive"))
    )
    (net (code "84") (name "unconnected-(*-USIM_DET-Pad53)") (class "Default")
      (node (ref "*") (pin "53") (pinfunction "USIM_DET_53") (pintype "passive"))
    )
    (net (code "85") (name "unconnected-(*-VBAT-Pad38)") (class "Default")
      (node (ref "*") (pin "38") (pinfunction "VBAT_38") (pintype "passive"))
    )
    (net (code "86") (name "unconnected-(*-VBAT-Pad39)") (class "Default")
      (node (ref "*") (pin "39") (pinfunction "VBAT_39") (pintype "passive"))
    )
    (net (code "87") (name "unconnected-(*-VDD_AUX-Pad44)") (class "Default")
      (node (ref "*") (pin "44") (pinfunction "VDD_AUX_44") (pintype "passive"))
    )
    (net (code "88") (name "unconnected-(CON4-VPP-Pad6)") (class "Default")
      (node (ref "CON4") (pin "6") (pinfunction "VPP_6") (pintype "passive"))
    )
    (net (code "89") (name "unconnected-(U2-K1-Pad1)") (class "Default")
      (node (ref "U2") (pin "1") (pinfunction "K1_1") (pintype "passive"))
    )
  )
)
